# openmv.net
KiCad netlist of a schematic drawn in EAGLE
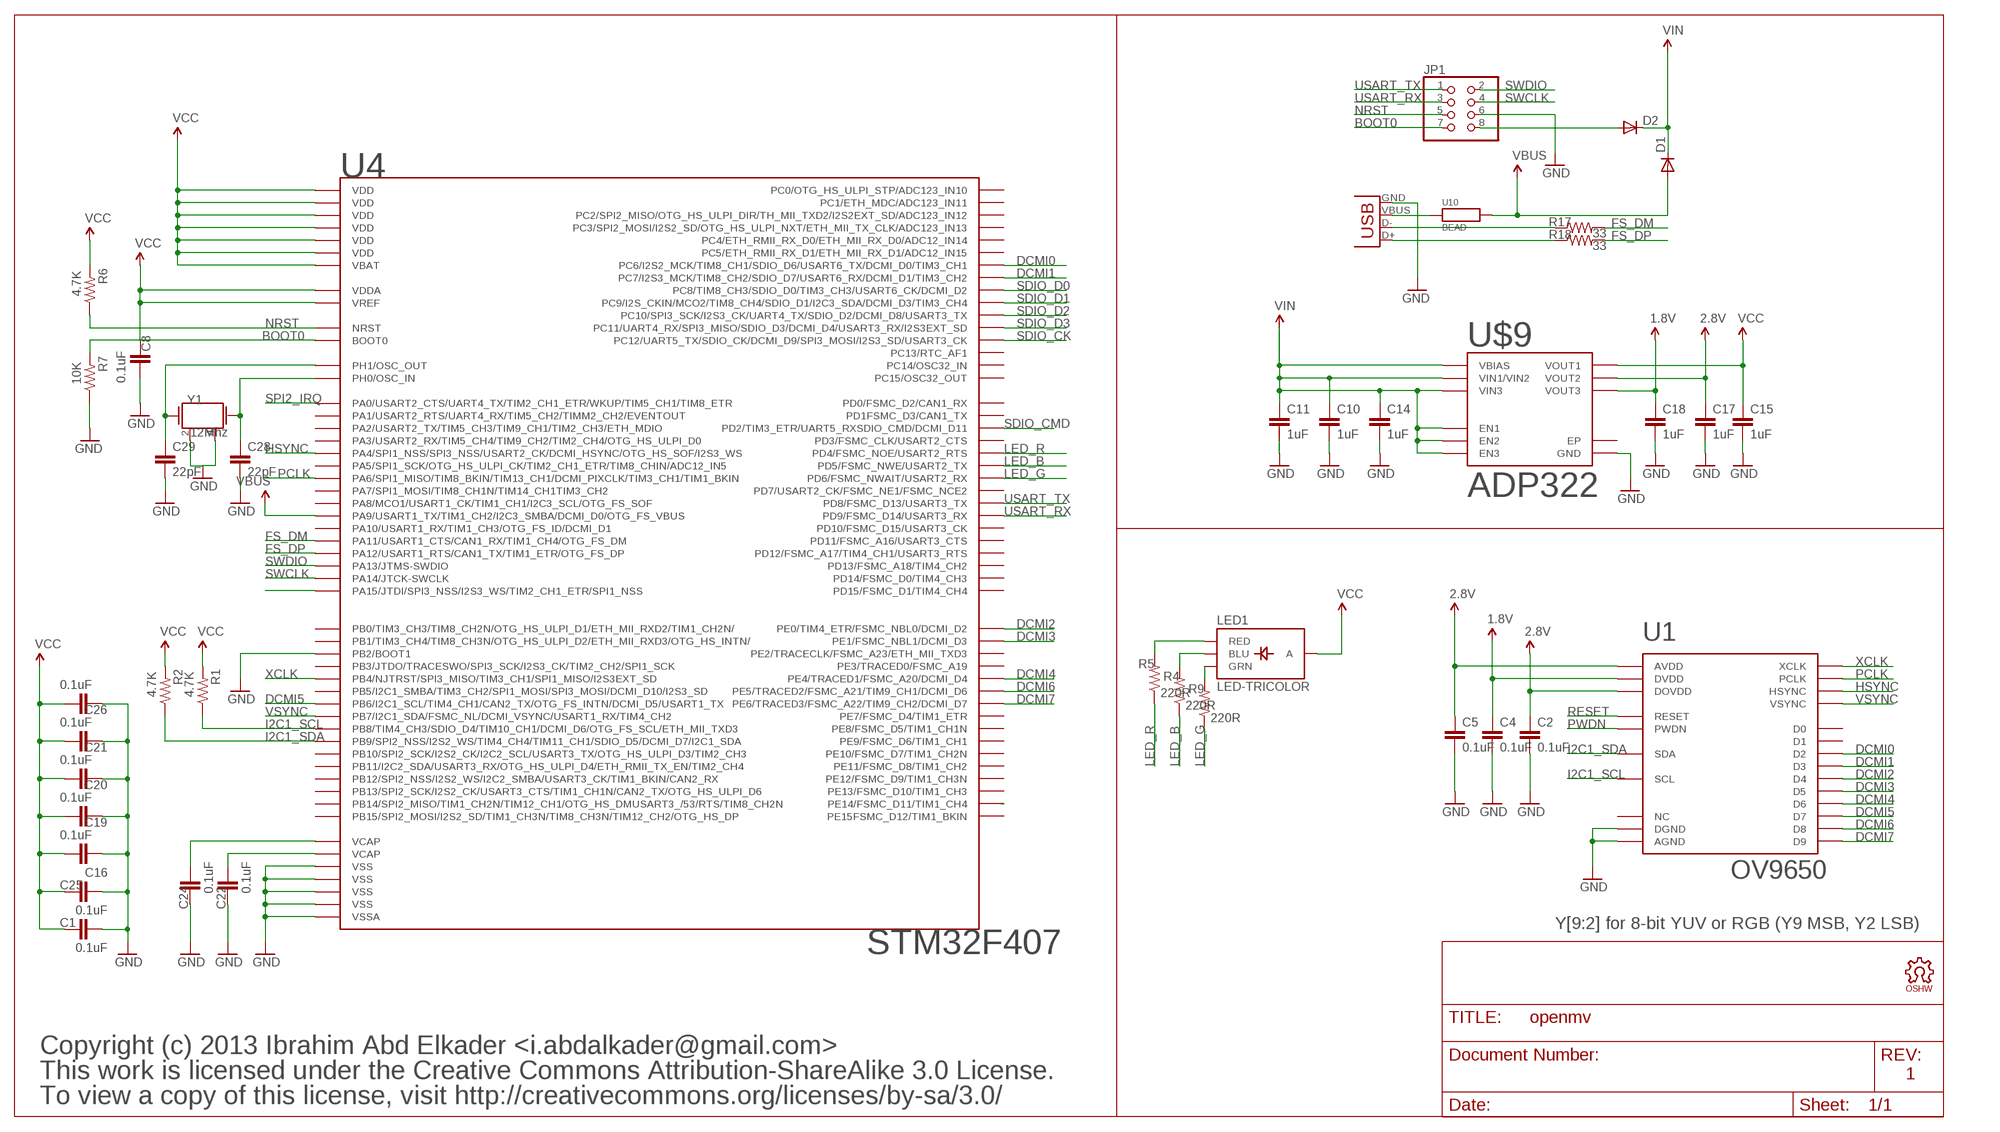
[diagram p0: schematic, sheet 1]

(export (version "E")
  (design (tool "Eeschema 10.0.6"))
  (components
    (comp (ref "C1")
      (value "0.1uF")
      (footprint "eagle-import:0402-CAP")
      (libsource (lib "eagle-import") (part "CAP0402-CAP"))
    )
    (comp (ref "C2")
      (value "0.1uF")
      (footprint "eagle-import:0402-CAP")
      (libsource (lib "eagle-import") (part "CAP0402-CAP"))
    )
    (comp (ref "C4")
      (value "0.1uF")
      (footprint "eagle-import:0402-CAP")
      (libsource (lib "eagle-import") (part "CAP0402-CAP"))
    )
    (comp (ref "C5")
      (value "0.1uF")
      (footprint "eagle-import:0402-CAP")
      (libsource (lib "eagle-import") (part "CAP0402-CAP"))
    )
    (comp (ref "C8")
      (value "0.1uF")
      (footprint "eagle-import:0402-CAP")
      (libsource (lib "eagle-import") (part "CAP0402-CAP"))
    )
    (comp (ref "C10")
      (value "1uF")
      (footprint "eagle-import:0402-CAP")
      (libsource (lib "eagle-import") (part "CAP0402-CAP"))
    )
    (comp (ref "C11")
      (value "1uF")
      (footprint "eagle-import:0402-CAP")
      (libsource (lib "eagle-import") (part "CAP0402-CAP"))
    )
    (comp (ref "C14")
      (value "1uF")
      (footprint "eagle-import:0402-CAP")
      (libsource (lib "eagle-import") (part "CAP0402-CAP"))
    )
    (comp (ref "C15")
      (value "1uF")
      (footprint "eagle-import:0402-CAP")
      (libsource (lib "eagle-import") (part "CAP0402-CAP"))
    )
    (comp (ref "C16")
      (value "0.1uF")
      (footprint "eagle-import:0402-CAP")
      (libsource (lib "eagle-import") (part "CAP0402-CAP"))
    )
    (comp (ref "C17")
      (value "1uF")
      (footprint "eagle-import:0402-CAP")
      (libsource (lib "eagle-import") (part "CAP0402-CAP"))
    )
    (comp (ref "C18")
      (value "1uF")
      (footprint "eagle-import:0402-CAP")
      (libsource (lib "eagle-import") (part "CAP0402-CAP"))
    )
    (comp (ref "C19")
      (value "0.1uF")
      (footprint "eagle-import:0402-CAP")
      (libsource (lib "eagle-import") (part "CAP0402-CAP"))
    )
    (comp (ref "C20")
      (value "0.1uF")
      (footprint "eagle-import:0402-CAP")
      (libsource (lib "eagle-import") (part "CAP0402-CAP"))
    )
    (comp (ref "C21")
      (value "0.1uF")
      (footprint "eagle-import:0402-CAP")
      (libsource (lib "eagle-import") (part "CAP0402-CAP"))
    )
    (comp (ref "C22")
      (value "0.1uF")
      (footprint "eagle-import:0402-CAP")
      (libsource (lib "eagle-import") (part "CAP0402-CAP"))
    )
    (comp (ref "C24")
      (value "0.1uF")
      (footprint "eagle-import:0402-CAP")
      (libsource (lib "eagle-import") (part "CAP0402-CAP"))
    )
    (comp (ref "C25")
      (value "0.1uF")
      (footprint "eagle-import:0402-CAP")
      (libsource (lib "eagle-import") (part "CAP0402-CAP"))
    )
    (comp (ref "C26")
      (value "0.1uF")
      (footprint "eagle-import:0402-CAP")
      (libsource (lib "eagle-import") (part "CAP0402-CAP"))
    )
    (comp (ref "C28")
      (value "22pF")
      (footprint "eagle-import:0402-CAP")
      (libsource (lib "eagle-import") (part "CAP0402-CAP"))
    )
    (comp (ref "C29")
      (value "22pF")
      (footprint "eagle-import:0402-CAP")
      (libsource (lib "eagle-import") (part "CAP0402-CAP"))
    )
    (comp (ref "D1")
      (value "DIODESOD")
      (footprint "eagle-import:SOD-323")
      (libsource (lib "eagle-import") (part "DIODESOD"))
    )
    (comp (ref "D2")
      (value "DIODESOD")
      (footprint "eagle-import:SOD-323")
      (libsource (lib "eagle-import") (part "DIODESOD"))
    )
    (comp (ref "JP1")
      (value "PINHD-2X4")
      (footprint "eagle-import:2X04")
      (libsource (lib "eagle-import") (part "PINHD-2X4"))
    )
    (comp (ref "LED1")
      (value "LED-TRICOLOR")
      (footprint "eagle-import:LED-TRICOLOR-SMD")
      (libsource (lib "eagle-import") (part "LED-TRICOLOR"))
    )
    (comp (ref "LOGO2")
      (value "OSHW_LOGO_FILLX0100-NT")
      (footprint "eagle-import:OSHW_FILLX100_NOTEXT")
      (libsource (lib "eagle-import") (part "OSHW_LOGO_FILLX0100-NT"))
    )
    (comp (ref "R1")
      (value "4.7K")
      (footprint "eagle-import:0402-RES")
      (libsource (lib "eagle-import") (part "RESISTOR0402-RES"))
    )
    (comp (ref "R2")
      (value "4.7K")
      (footprint "eagle-import:0402-RES")
      (libsource (lib "eagle-import") (part "RESISTOR0402-RES"))
    )
    (comp (ref "R4")
      (value "220R")
      (footprint "eagle-import:0402-RES")
      (libsource (lib "eagle-import") (part "RESISTOR0402-RES"))
    )
    (comp (ref "R5")
      (value "220R")
      (footprint "eagle-import:0402-RES")
      (libsource (lib "eagle-import") (part "RESISTOR0402-RES"))
    )
    (comp (ref "R6")
      (value "4.7K")
      (footprint "eagle-import:0402-RES")
      (libsource (lib "eagle-import") (part "RESISTOR0402-RES"))
    )
    (comp (ref "R7")
      (value "10K")
      (footprint "eagle-import:0402-RES")
      (libsource (lib "eagle-import") (part "RESISTOR0402-RES"))
    )
    (comp (ref "R9")
      (value "220R")
      (footprint "eagle-import:0402-RES")
      (libsource (lib "eagle-import") (part "RESISTOR0402-RES"))
    )
    (comp (ref "R17")
      (value "33")
      (footprint "eagle-import:0402-RES")
      (libsource (lib "eagle-import") (part "RESISTOR0402-RES"))
    )
    (comp (ref "R18")
      (value "33")
      (footprint "eagle-import:0402-RES")
      (libsource (lib "eagle-import") (part "RESISTOR0402-RES"))
    )
    (comp (ref "U$9")
      (value "ADP322")
      (footprint "eagle-import:WFQFN-16")
      (libsource (lib "eagle-import") (part "ADP322"))
    )
    (comp (ref "U1")
      (value "OV9650")
      (footprint "eagle-import:OV9650")
      (libsource (lib "eagle-import") (part "OV9650"))
    )
    (comp (ref "U4")
      (value "STM32F407")
      (footprint "eagle-import:LQFP100")
      (libsource (lib "eagle-import") (part "STM32F407"))
    )
    (comp (ref "U10")
      (value "BEAD")
      (footprint "eagle-import:0402-CAP")
      (libsource (lib "eagle-import") (part "BEAD"))
    )
    (comp (ref "X2")
      (value "USB-MICROB")
      (footprint "eagle-import:USB-MICROB")
      (libsource (lib "eagle-import") (part "USB-MICROB"))
    )
    (comp (ref "Y1")
      (value "12Mhz")
      (footprint "eagle-import:CRYSTAL-SMD-5X3")
      (libsource (lib "eagle-import") (part "CRYSTAL5X3"))
    )
  )
  (nets
    (net (code "1") (name "/BOOT0") (class "Default")
      (node (ref "JP1") (pin "7") (pinfunction "7_7") (pintype "passive"))
      (node (ref "R7") (pin "2") (pinfunction "2_2") (pintype "passive"))
      (node (ref "U4") (pin "94") (pinfunction "BOOT0_94") (pintype "bidirectional"))
    )
    (net (code "2") (name "/DCMI0") (class "Default")
      (node (ref "U1") (pin "P$19") (pinfunction "D2_P$19") (pintype "bidirectional"))
      (node (ref "U4") (pin "63") (pinfunction "PC6/I2S2_MCK/TIM8_CH1/SDIO_D6/USART6_TX/DCMI_D0/TIM3_CH1_63") (pintype "bidirectional"))
    )
    (net (code "3") (name "/DCMI1") (class "Default")
      (node (ref "U1") (pin "P$21") (pinfunction "D3_P$21") (pintype "bidirectional"))
      (node (ref "U4") (pin "64") (pinfunction "PC7/I2S3_MCK/TIM8_CH2/SDIO_D7/USART6_RX/DCMI_D1/TIM3_CH2_64") (pintype "bidirectional"))
    )
    (net (code "4") (name "/DCMI2") (class "Default")
      (node (ref "U1") (pin "P$22") (pinfunction "D4_P$22") (pintype "bidirectional"))
      (node (ref "U4") (pin "97") (pinfunction "PE0/TIM4_ETR/FSMC_NBL0/DCMI_D2_97") (pintype "bidirectional"))
    )
    (net (code "5") (name "/DCMI3") (class "Default")
      (node (ref "U1") (pin "P$20") (pinfunction "D5_P$20") (pintype "bidirectional"))
      (node (ref "U4") (pin "98") (pinfunction "PE1/FSMC_NBL1/DCMI_D3_98") (pintype "bidirectional"))
    )
    (net (code "6") (name "/DCMI4") (class "Default")
      (node (ref "U1") (pin "P$18") (pinfunction "D6_P$18") (pintype "bidirectional"))
      (node (ref "U4") (pin "3") (pinfunction "PE4/TRACED1/FSMC_A20/DCMI_D4_3") (pintype "bidirectional"))
    )
    (net (code "7") (name "/DCMI5") (class "Default")
      (node (ref "U1") (pin "P$16") (pinfunction "D7_P$16") (pintype "bidirectional"))
      (node (ref "U4") (pin "92") (pinfunction "PB6/I2C1_SCL/TIM4_CH1/CAN2_TX/OTG_FS_INTN/DCMI_D5/USART1_TX_92") (pintype "bidirectional"))
    )
    (net (code "8") (name "/DCMI6") (class "Default")
      (node (ref "U1") (pin "P$14") (pinfunction "D8_P$14") (pintype "bidirectional"))
      (node (ref "U4") (pin "4") (pinfunction "PE5/TRACED2/FSMC_A21/TIM9_CH1/DCMI_D6_4") (pintype "bidirectional"))
    )
    (net (code "9") (name "/DCMI7") (class "Default")
      (node (ref "U1") (pin "P$12") (pinfunction "D9_P$12") (pintype "bidirectional"))
      (node (ref "U4") (pin "5") (pinfunction "PE6/TRACED3/FSMC_A22/TIM9_CH2/DCMI_D7_5") (pintype "bidirectional"))
    )
    (net (code "10") (name "/FS_DM") (class "Default")
      (node (ref "R17") (pin "2") (pinfunction "2_2") (pintype "passive"))
      (node (ref "U4") (pin "70") (pinfunction "PA11/USART1_CTS/CAN1_RX/TIM1_CH4/OTG_FS_DM_70") (pintype "bidirectional"))
    )
    (net (code "11") (name "/FS_DP") (class "Default")
      (node (ref "R18") (pin "2") (pinfunction "2_2") (pintype "passive"))
      (node (ref "U4") (pin "71") (pinfunction "PA12/USART1_RTS/CAN1_TX/TIM1_ETR/OTG_FS_DP_71") (pintype "bidirectional"))
    )
    (net (code "12") (name "/HSYNC") (class "Default")
      (node (ref "U1") (pin "P$9") (pinfunction "HSYNC_P$9") (pintype "bidirectional"))
      (node (ref "U4") (pin "29") (pinfunction "PA4/SPI1_NSS/SPI3_NSS/USART2_CK/DCMI_HSYNC/OTG_HS_SOF/I2S3_WS_29") (pintype "bidirectional"))
    )
    (net (code "13") (name "/I2C1_SCL") (class "Default")
      (node (ref "R1") (pin "1") (pinfunction "1_1") (pintype "passive"))
      (node (ref "U1") (pin "P$5") (pinfunction "SCL_P$5") (pintype "bidirectional"))
      (node (ref "U4") (pin "95") (pinfunction "PB8/TIM4_CH3/SDIO_D4/TIM10_CH1/DCMI_D6/OTG_FS_SCL/ETH_MII_TXD3_95") (pintype "bidirectional"))
    )
    (net (code "14") (name "/I2C1_SDA") (class "Default")
      (node (ref "R2") (pin "1") (pinfunction "1_1") (pintype "passive"))
      (node (ref "U1") (pin "P$3") (pinfunction "SDA_P$3") (pintype "bidirectional"))
      (node (ref "U4") (pin "96") (pinfunction "PB9/SPI2_NSS/I2S2_WS/TIM4_CH4/TIM11_CH1/SDIO_D5/DCMI_D7/I2C1_SDA_96") (pintype "bidirectional"))
    )
    (net (code "15") (name "/LED_B") (class "Default")
      (node (ref "R4") (pin "1") (pinfunction "1_1") (pintype "passive"))
      (node (ref "U4") (pin "86") (pinfunction "PD5/FSMC_NWE/USART2_TX_86") (pintype "bidirectional"))
    )
    (net (code "16") (name "/LED_G") (class "Default")
      (node (ref "R9") (pin "1") (pinfunction "1_1") (pintype "passive"))
      (node (ref "U4") (pin "87") (pinfunction "PD6/FSMC_NWAIT/USART2_RX_87") (pintype "bidirectional"))
    )
    (net (code "17") (name "/LED_R") (class "Default")
      (node (ref "R5") (pin "1") (pinfunction "1_1") (pintype "passive"))
      (node (ref "U4") (pin "85") (pinfunction "PD4/FSMC_NOE/USART2_RTS_85") (pintype "bidirectional"))
    )
    (net (code "18") (name "/NRST") (class "Default")
      (node (ref "JP1") (pin "5") (pinfunction "5_5") (pintype "passive"))
      (node (ref "R6") (pin "1") (pinfunction "1_1") (pintype "passive"))
      (node (ref "U4") (pin "14") (pinfunction "NRST_14") (pintype "bidirectional"))
    )
    (net (code "19") (name "/PCLK") (class "Default")
      (node (ref "U1") (pin "P$17") (pinfunction "PCLK_P$17") (pintype "bidirectional"))
      (node (ref "U4") (pin "31") (pinfunction "PA6/SPI1_MISO/TIM8_BKIN/TIM13_CH1/DCMI_PIXCLK/TIM3_CH1/TIM1_BKIN_31") (pintype "bidirectional"))
    )
    (net (code "20") (name "/PWDN") (class "Default")
      (node (ref "U1") (pin "P$8") (pinfunction "PWDN_P$8") (pintype "bidirectional"))
    )
    (net (code "21") (name "/RESET") (class "Default")
      (node (ref "U1") (pin "P$6") (pinfunction "RESET_P$6") (pintype "bidirectional"))
    )
    (net (code "22") (name "/SDIO_CK") (class "Default")
      (node (ref "U4") (pin "80") (pinfunction "PC12/UART5_TX/SDIO_CK/DCMI_D9/SPI3_MOSI/I2S3_SD/USART3_CK_80") (pintype "bidirectional"))
    )
    (net (code "23") (name "/SDIO_CMD") (class "Default")
      (node (ref "U4") (pin "83") (pinfunction "PD2/TIM3_ETR/UART5_RXSDIO_CMD/DCMI_D11_83") (pintype "bidirectional"))
    )
    (net (code "24") (name "/SDIO_D0") (class "Default")
      (node (ref "U4") (pin "65") (pinfunction "PC8/TIM8_CH3/SDIO_D0/TIM3_CH3/USART6_CK/DCMI_D2_65") (pintype "bidirectional"))
    )
    (net (code "25") (name "/SDIO_D1") (class "Default")
      (node (ref "U4") (pin "66") (pinfunction "PC9/I2S_CKIN/MCO2/TIM8_CH4/SDIO_D1/I2C3_SDA/DCMI_D3/TIM3_CH4_66") (pintype "bidirectional"))
    )
    (net (code "26") (name "/SDIO_D2") (class "Default")
      (node (ref "U4") (pin "78") (pinfunction "PC10/SPI3_SCK/I2S3_CK/UART4_TX/SDIO_D2/DCMI_D8/USART3_TX_78") (pintype "bidirectional"))
    )
    (net (code "27") (name "/SDIO_D3") (class "Default")
      (node (ref "U4") (pin "79") (pinfunction "PC11/UART4_RX/SPI3_MISO/SDIO_D3/DCMI_D4/USART3_RX/I2S3EXT_SD_79") (pintype "bidirectional"))
    )
    (net (code "28") (name "/SPI2_IRQ") (class "Default")
      (node (ref "U4") (pin "23") (pinfunction "PA0/USART2_CTS/UART4_TX/TIM2_CH1_ETR/WKUP/TIM5_CH1/TIM8_ETR_23") (pintype "bidirectional"))
    )
    (net (code "29") (name "/SWCLK") (class "Default")
      (node (ref "JP1") (pin "4") (pinfunction "4_4") (pintype "passive"))
      (node (ref "U4") (pin "76") (pinfunction "PA14/JTCK-SWCLK_76") (pintype "bidirectional"))
    )
    (net (code "30") (name "/SWDIO") (class "Default")
      (node (ref "JP1") (pin "2") (pinfunction "2_2") (pintype "passive"))
      (node (ref "U4") (pin "72") (pinfunction "PA13/JTMS-SWDIO_72") (pintype "bidirectional"))
    )
    (net (code "31") (name "/USART_RX") (class "Default")
      (node (ref "JP1") (pin "3") (pinfunction "3_3") (pintype "passive"))
      (node (ref "U4") (pin "56") (pinfunction "PD9/FSMC_D14/USART3_RX_56") (pintype "bidirectional"))
    )
    (net (code "32") (name "/USART_TX") (class "Default")
      (node (ref "JP1") (pin "1") (pinfunction "1_1") (pintype "passive"))
      (node (ref "U4") (pin "55") (pinfunction "PD8/FSMC_D13/USART3_TX_55") (pintype "bidirectional"))
    )
    (net (code "33") (name "/VSYNC") (class "Default")
      (node (ref "U1") (pin "P$7") (pinfunction "VSYNC_P$7") (pintype "bidirectional"))
      (node (ref "U4") (pin "93") (pinfunction "PB7/I2C1_SDA/FSMC_NL/DCMI_VSYNC/USART1_RX/TIM4_CH2_93") (pintype "bidirectional"))
    )
    (net (code "34") (name "/XCLK") (class "Default")
      (node (ref "U1") (pin "P$13") (pinfunction "XCLK_P$13") (pintype "bidirectional"))
      (node (ref "U4") (pin "90") (pinfunction "PB4/NJTRST/SPI3_MISO/TIM3_CH1/SPI1_MISO/I2S3EXT_SD_90") (pintype "bidirectional"))
    )
    (net (code "35") (name "1.8V") (class "Default")
      (node (ref "C18") (pin "1") (pinfunction "1_1") (pintype "passive"))
      (node (ref "C4") (pin "1") (pinfunction "1_1") (pintype "passive"))
      (node (ref "U$9") (pin "8") (pinfunction "VOUT3_8") (pintype "passive"))
      (node (ref "U1") (pin "P$10") (pinfunction "DVDD_P$10") (pintype "bidirectional"))
    )
    (net (code "36") (name "2.8V") (class "Default")
      (node (ref "C17") (pin "1") (pinfunction "1_1") (pintype "passive"))
      (node (ref "C2") (pin "1") (pinfunction "1_1") (pintype "passive"))
      (node (ref "C5") (pin "1") (pinfunction "1_1") (pintype "passive"))
      (node (ref "U$9") (pin "6") (pinfunction "VOUT2_6") (pintype "passive"))
      (node (ref "U1") (pin "P$11") (pinfunction "DOVDD_P$11") (pintype "bidirectional"))
      (node (ref "U1") (pin "P$4") (pinfunction "AVDD_P$4") (pintype "power_in"))
    )
    (net (code "37") (name "GND") (class "Default")
      (node (ref "C1") (pin "1") (pinfunction "1_1") (pintype "passive"))
      (node (ref "C10") (pin "2") (pinfunction "2_2") (pintype "passive"))
      (node (ref "C11") (pin "2") (pinfunction "2_2") (pintype "passive"))
      (node (ref "C14") (pin "2") (pinfunction "2_2") (pintype "passive"))
      (node (ref "C15") (pin "2") (pinfunction "2_2") (pintype "passive"))
      (node (ref "C16") (pin "1") (pinfunction "1_1") (pintype "passive"))
      (node (ref "C17") (pin "2") (pinfunction "2_2") (pintype "passive"))
      (node (ref "C18") (pin "2") (pinfunction "2_2") (pintype "passive"))
      (node (ref "C19") (pin "2") (pinfunction "2_2") (pintype "passive"))
      (node (ref "C2") (pin "2") (pinfunction "2_2") (pintype "passive"))
      (node (ref "C20") (pin "2") (pinfunction "2_2") (pintype "passive"))
      (node (ref "C21") (pin "2") (pinfunction "2_2") (pintype "passive"))
      (node (ref "C22") (pin "2") (pinfunction "2_2") (pintype "passive"))
      (node (ref "C24") (pin "2") (pinfunction "2_2") (pintype "passive"))
      (node (ref "C25") (pin "1") (pinfunction "1_1") (pintype "passive"))
      (node (ref "C26") (pin "2") (pinfunction "2_2") (pintype "passive"))
      (node (ref "C28") (pin "2") (pinfunction "2_2") (pintype "passive"))
      (node (ref "C29") (pin "2") (pinfunction "2_2") (pintype "passive"))
      (node (ref "C4") (pin "2") (pinfunction "2_2") (pintype "passive"))
      (node (ref "C5") (pin "2") (pinfunction "2_2") (pintype "passive"))
      (node (ref "C8") (pin "1") (pinfunction "1_1") (pintype "passive"))
      (node (ref "JP1") (pin "6") (pinfunction "6_6") (pintype "passive"))
      (node (ref "R7") (pin "1") (pinfunction "1_1") (pintype "passive"))
      (node (ref "U$9") (pin "12") (pinfunction "GND_12") (pintype "power_in"))
      (node (ref "U1") (pin "P$15") (pinfunction "DGND_P$15") (pintype "bidirectional"))
      (node (ref "U1") (pin "P$2") (pinfunction "AGND_P$2") (pintype "power_in"))
      (node (ref "U4") (pin "10") (pinfunction "VSS_10") (pintype "power_in"))
      (node (ref "U4") (pin "20") (pinfunction "VSSA_20") (pintype "power_in"))
      (node (ref "U4") (pin "27") (pinfunction "VSS_27") (pintype "power_in"))
      (node (ref "U4") (pin "37") (pinfunction "PB2/BOOT1_37") (pintype "bidirectional"))
      (node (ref "U4") (pin "74") (pinfunction "VSS_74") (pintype "power_in"))
      (node (ref "U4") (pin "99") (pinfunction "VSS_99") (pintype "power_in"))
      (node (ref "X2") (pin "GND") (pinfunction "GND_GND") (pintype "bidirectional"))
      (node (ref "Y1") (pin "2") (pinfunction "P$1_2") (pintype "power_in"))
      (node (ref "Y1") (pin "4") (pinfunction "P$2_4") (pintype "power_in"))
    )
    (net (code "38") (name "Net-(C22-Pad1)") (class "Default")
      (node (ref "C22") (pin "1") (pinfunction "1_1") (pintype "passive"))
      (node (ref "U4") (pin "73") (pinfunction "VCAP_73") (pintype "power_in"))
    )
    (net (code "39") (name "Net-(C24-Pad1)") (class "Default")
      (node (ref "C24") (pin "1") (pinfunction "1_1") (pintype "passive"))
      (node (ref "U4") (pin "49") (pinfunction "VCAP_49") (pintype "power_in"))
    )
    (net (code "40") (name "Net-(D2-A)") (class "Default")
      (node (ref "D2") (pin "2") (pinfunction "A_2") (pintype "passive"))
      (node (ref "JP1") (pin "8") (pinfunction "8_8") (pintype "passive"))
    )
    (net (code "41") (name "Net-(LED1-BLU)") (class "Default")
      (node (ref "LED1") (pin "B") (pinfunction "BLU_B") (pintype "bidirectional"))
      (node (ref "R4") (pin "2") (pinfunction "2_2") (pintype "passive"))
    )
    (net (code "42") (name "Net-(LED1-GRN)") (class "Default")
      (node (ref "LED1") (pin "G") (pinfunction "GRN_G") (pintype "bidirectional"))
      (node (ref "R9") (pin "2") (pinfunction "2_2") (pintype "passive"))
    )
    (net (code "43") (name "Net-(LED1-RED)") (class "Default")
      (node (ref "LED1") (pin "R") (pinfunction "RED_R") (pintype "bidirectional"))
      (node (ref "R5") (pin "2") (pinfunction "2_2") (pintype "passive"))
    )
    (net (code "44") (name "Net-(R17-Pad1)") (class "Default")
      (node (ref "R17") (pin "1") (pinfunction "1_1") (pintype "passive"))
      (node (ref "X2") (pin "D-") (pinfunction "D-_D-") (pintype "bidirectional"))
    )
    (net (code "45") (name "Net-(R18-Pad1)") (class "Default")
      (node (ref "R18") (pin "1") (pinfunction "1_1") (pintype "passive"))
      (node (ref "X2") (pin "D+") (pinfunction "D+_D+") (pintype "bidirectional"))
    )
    (net (code "46") (name "Net-(U4-PH0{slash}OSC_IN)") (class "Default")
      (node (ref "C28") (pin "1") (pinfunction "1_1") (pintype "passive"))
      (node (ref "U4") (pin "12") (pinfunction "PH0/OSC_IN_12") (pintype "bidirectional"))
      (node (ref "Y1") (pin "3") (pinfunction "2_3") (pintype "passive"))
    )
    (net (code "47") (name "Net-(U4-PH1{slash}OSC_OUT)") (class "Default")
      (node (ref "C29") (pin "1") (pinfunction "1_1") (pintype "passive"))
      (node (ref "U4") (pin "13") (pinfunction "PH1/OSC_OUT_13") (pintype "bidirectional"))
      (node (ref "Y1") (pin "1") (pinfunction "1_1") (pintype "passive"))
    )
    (net (code "48") (name "Net-(U10-Pad1)") (class "Default")
      (node (ref "U10") (pin "1") (pinfunction "1_1") (pintype "passive"))
      (node (ref "X2") (pin "VBUS") (pinfunction "VBUS_VBUS") (pintype "bidirectional"))
    )
    (net (code "49") (name "VBUS") (class "Default")
      (node (ref "D1") (pin "2") (pinfunction "A_2") (pintype "passive"))
      (node (ref "U10") (pin "2") (pinfunction "2_2") (pintype "passive"))
      (node (ref "U4") (pin "68") (pinfunction "PA9/USART1_TX/TIM1_CH2/I2C3_SMBA/DCMI_D0/OTG_FS_VBUS_68") (pintype "bidirectional"))
    )
    (net (code "50") (name "VCC") (class "Default")
      (node (ref "C1") (pin "2") (pinfunction "2_2") (pintype "passive"))
      (node (ref "C15") (pin "1") (pinfunction "1_1") (pintype "passive"))
      (node (ref "C16") (pin "2") (pinfunction "2_2") (pintype "passive"))
      (node (ref "C19") (pin "1") (pinfunction "1_1") (pintype "passive"))
      (node (ref "C20") (pin "1") (pinfunction "1_1") (pintype "passive"))
      (node (ref "C21") (pin "1") (pinfunction "1_1") (pintype "passive"))
      (node (ref "C25") (pin "2") (pinfunction "2_2") (pintype "passive"))
      (node (ref "C26") (pin "1") (pinfunction "1_1") (pintype "passive"))
      (node (ref "C8") (pin "2") (pinfunction "2_2") (pintype "passive"))
      (node (ref "LED1") (pin "A") (pinfunction "A_A") (pintype "bidirectional"))
      (node (ref "R1") (pin "2") (pinfunction "2_2") (pintype "passive"))
      (node (ref "R2") (pin "2") (pinfunction "2_2") (pintype "passive"))
      (node (ref "R6") (pin "2") (pinfunction "2_2") (pintype "passive"))
      (node (ref "U$9") (pin "5") (pinfunction "VOUT1_5") (pintype "passive"))
      (node (ref "U4") (pin "100") (pinfunction "VDD_100") (pintype "power_in"))
      (node (ref "U4") (pin "11") (pinfunction "VDD_11") (pintype "power_in"))
      (node (ref "U4") (pin "19") (pinfunction "VDD_19") (pintype "power_in"))
      (node (ref "U4") (pin "21") (pinfunction "VREF_21") (pintype "power_in"))
      (node (ref "U4") (pin "22") (pinfunction "VDDA_22") (pintype "power_in"))
      (node (ref "U4") (pin "28") (pinfunction "VDD_28") (pintype "power_in"))
      (node (ref "U4") (pin "50") (pinfunction "VDD_50") (pintype "power_in"))
      (node (ref "U4") (pin "6") (pinfunction "VBAT_6") (pintype "power_in"))
      (node (ref "U4") (pin "75") (pinfunction "VDD_75") (pintype "power_in"))
    )
    (net (code "51") (name "VIN") (class "Default")
      (node (ref "C10") (pin "1") (pinfunction "1_1") (pintype "passive"))
      (node (ref "C11") (pin "1") (pinfunction "1_1") (pintype "passive"))
      (node (ref "C14") (pin "1") (pinfunction "1_1") (pintype "passive"))
      (node (ref "D1") (pin "1") (pinfunction "C_1") (pintype "passive"))
      (node (ref "D2") (pin "1") (pinfunction "C_1") (pintype "passive"))
      (node (ref "U$9") (pin "1") (pinfunction "EN1_1") (pintype "passive"))
      (node (ref "U$9") (pin "10") (pinfunction "VIN3_10") (pintype "power_in"))
      (node (ref "U$9") (pin "15") (pinfunction "EN3_15") (pintype "passive"))
      (node (ref "U$9") (pin "16") (pinfunction "EN2_16") (pintype "passive"))
      (node (ref "U$9") (pin "2") (pinfunction "VBIAS_2") (pintype "power_in"))
      (node (ref "U$9") (pin "3") (pinfunction "VIN1/VIN2_3") (pintype "power_in"))
    )
    (net (code "52") (name "unconnected-(U$9A-EP-PadEXP)") (class "Default")
      (node (ref "U$9") (pin "EXP") (pinfunction "EP_EXP") (pintype "input"))
    )
    (net (code "53") (name "unconnected-(U1-D0-PadP$24)") (class "Default")
      (node (ref "U1") (pin "P$24") (pinfunction "D0_P$24") (pintype "bidirectional"))
    )
    (net (code "54") (name "unconnected-(U1-D1-PadP$23)") (class "Default")
      (node (ref "U1") (pin "P$23") (pinfunction "D1_P$23") (pintype "bidirectional"))
    )
    (net (code "55") (name "unconnected-(U1-NC-PadP$1)") (class "Default")
      (node (ref "U1") (pin "P$1") (pinfunction "NC_P$1") (pintype "no_connect"))
    )
    (net (code "56") (name "unconnected-(U4-PA1{slash}USART2_RTS{slash}UART4_RX{slash}TIM5_CH2{slash}TIMM2_CH2{slash}EVENTOUT-Pad24)") (class "Default")
      (node (ref "U4") (pin "24") (pinfunction "PA1/USART2_RTS/UART4_RX/TIM5_CH2/TIMM2_CH2/EVENTOUT_24") (pintype "bidirectional"))
    )
    (net (code "57") (name "unconnected-(U4-PA2{slash}USART2_TX{slash}TIM5_CH3{slash}TIM9_CH1{slash}TIM2_CH3{slash}ETH_MDIO-Pad25)") (class "Default")
      (node (ref "U4") (pin "25") (pinfunction "PA2/USART2_TX/TIM5_CH3/TIM9_CH1/TIM2_CH3/ETH_MDIO_25") (pintype "bidirectional"))
    )
    (net (code "58") (name "unconnected-(U4-PA3{slash}USART2_RX{slash}TIM5_CH4{slash}TIM9_CH2{slash}TIM2_CH4{slash}OTG_HS_ULPI_D0-Pad26)") (class "Default")
      (node (ref "U4") (pin "26") (pinfunction "PA3/USART2_RX/TIM5_CH4/TIM9_CH2/TIM2_CH4/OTG_HS_ULPI_D0_26") (pintype "bidirectional"))
    )
    (net (code "59") (name "unconnected-(U4-PA5{slash}SPI1_SCK{slash}OTG_HS_ULPI_CK{slash}TIM2_CH1_ETR{slash}TIM8_CHIN{slash}ADC12_IN5-Pad30)") (class "Default")
      (node (ref "U4") (pin "30") (pinfunction "PA5/SPI1_SCK/OTG_HS_ULPI_CK/TIM2_CH1_ETR/TIM8_CHIN/ADC12_IN5_30") (pintype "bidirectional"))
    )
    (net (code "60") (name "unconnected-(U4-PA7{slash}SPI1_MOSI{slash}TIM8_CH1N{slash}TIM14_CH1TIM3_CH2-Pad32)") (class "Default")
      (node (ref "U4") (pin "32") (pinfunction "PA7/SPI1_MOSI/TIM8_CH1N/TIM14_CH1TIM3_CH2_32") (pintype "bidirectional"))
    )
    (net (code "61") (name "unconnected-(U4-PA8{slash}MCO1{slash}USART1_CK{slash}TIM1_CH1{slash}I2C3_SCL{slash}OTG_FS_SOF-Pad67)") (class "Default")
      (node (ref "U4") (pin "67") (pinfunction "PA8/MCO1/USART1_CK/TIM1_CH1/I2C3_SCL/OTG_FS_SOF_67") (pintype "bidirectional"))
    )
    (net (code "62") (name "unconnected-(U4-PA10{slash}USART1_RX{slash}TIM1_CH3{slash}OTG_FS_ID{slash}DCMI_D1-Pad69)") (class "Default")
      (node (ref "U4") (pin "69") (pinfunction "PA10/USART1_RX/TIM1_CH3/OTG_FS_ID/DCMI_D1_69") (pintype "bidirectional"))
    )
    (net (code "63") (name "unconnected-(U4-PA15{slash}JTDI{slash}SPI3_NSS{slash}I2S3_WS{slash}TIM2_CH1_ETR{slash}SPI1_NSS-Pad77)") (class "Default")
      (node (ref "U4") (pin "77") (pinfunction "PA15/JTDI/SPI3_NSS/I2S3_WS/TIM2_CH1_ETR/SPI1_NSS_77") (pintype "bidirectional"))
    )
    (net (code "64") (name "unconnected-(U4-PB0{slash}TIM3_CH3{slash}TIM8_CH2N{slash}OTG_HS_ULPI_D1{slash}ETH_MII_RXD2{slash}TIM1_CH2N{slash}-Pad35)") (class "Default")
      (node (ref "U4") (pin "35") (pinfunction "PB0/TIM3_CH3/TIM8_CH2N/OTG_HS_ULPI_D1/ETH_MII_RXD2/TIM1_CH2N/_35") (pintype "bidirectional"))
    )
    (net (code "65") (name "unconnected-(U4-PB1{slash}TIM3_CH4{slash}TIM8_CH3N{slash}OTG_HS_ULPI_D2{slash}ETH_MII_RXD3{slash}OTG_HS_INTN{slash}-Pad36)") (class "Default")
      (node (ref "U4") (pin "36") (pinfunction "PB1/TIM3_CH4/TIM8_CH3N/OTG_HS_ULPI_D2/ETH_MII_RXD3/OTG_HS_INTN/_36") (pintype "bidirectional"))
    )
    (net (code "66") (name "unconnected-(U4-PB3{slash}JTDO{slash}TRACESWO{slash}SPI3_SCK{slash}I2S3_CK{slash}TIM2_CH2{slash}SPI1_SCK-Pad89)") (class "Default")
      (node (ref "U4") (pin "89") (pinfunction "PB3/JTDO/TRACESWO/SPI3_SCK/I2S3_CK/TIM2_CH2/SPI1_SCK_89") (pintype "bidirectional"))
    )
    (net (code "67") (name "unconnected-(U4-PB5{slash}I2C1_SMBA{slash}TIM3_CH2{slash}SPI1_MOSI{slash}SPI3_MOSI{slash}DCMI_D10{slash}I2S3_SD-Pad91)") (class "Default")
      (node (ref "U4") (pin "91") (pinfunction "PB5/I2C1_SMBA/TIM3_CH2/SPI1_MOSI/SPI3_MOSI/DCMI_D10/I2S3_SD_91") (pintype "bidirectional"))
    )
    (net (code "68") (name "unconnected-(U4-PB10{slash}SPI2_SCK{slash}I2S2_CK{slash}I2C2_SCL{slash}USART3_TX{slash}OTG_HS_ULPI_D3{slash}TIM2_CH3-Pad47)") (class "Default")
      (node (ref "U4") (pin "47") (pinfunction "PB10/SPI2_SCK/I2S2_CK/I2C2_SCL/USART3_TX/OTG_HS_ULPI_D3/TIM2_CH3_47") (pintype "bidirectional"))
    )
    (net (code "69") (name "unconnected-(U4-PB11{slash}I2C2_SDA{slash}USART3_RX{slash}OTG_HS_ULPI_D4{slash}ETH_RMII_TX_EN{slash}TIM2_CH4-Pad48)") (class "Default")
      (node (ref "U4") (pin "48") (pinfunction "PB11/I2C2_SDA/USART3_RX/OTG_HS_ULPI_D4/ETH_RMII_TX_EN/TIM2_CH4_48") (pintype "bidirectional"))
    )
    (net (code "70") (name "unconnected-(U4-PB12{slash}SPI2_NSS{slash}I2S2_WS{slash}I2C2_SMBA{slash}USART3_CK{slash}TIM1_BKIN{slash}CAN2_RX-Pad51)") (class "Default")
      (node (ref "U4") (pin "51") (pinfunction "PB12/SPI2_NSS/I2S2_WS/I2C2_SMBA/USART3_CK/TIM1_BKIN/CAN2_RX_51") (pintype "bidirectional"))
    )
    (net (code "71") (name "unconnected-(U4-PB13{slash}SPI2_SCK{slash}I2S2_CK{slash}USART3_CTS{slash}TIM1_CH1N{slash}CAN2_TX{slash}OTG_HS_ULPI_D6-Pad52)") (class "Default")
      (node (ref "U4") (pin "52") (pinfunction "PB13/SPI2_SCK/I2S2_CK/USART3_CTS/TIM1_CH1N/CAN2_TX/OTG_HS_ULPI_D6_52") (pintype "bidirectional"))
    )
    (net (code "72") (name "unconnected-(U4-PB14{slash}SPI2_MISO{slash}TIM1_CH2N{slash}TIM12_CH1{slash}OTG_HS_DMUSART3_{slash}53{slash}RTS{slash}TIM8_CH2N-Pad53)") (class "Default")
      (node (ref "U4") (pin "53") (pinfunction "PB14/SPI2_MISO/TIM1_CH2N/TIM12_CH1/OTG_HS_DMUSART3_/53/RTS/TIM8_CH2N_53") (pintype "bidirectional"))
    )
    (net (code "73") (name "unconnected-(U4-PB15{slash}SPI2_MOSI{slash}I2S2_SD{slash}TIM1_CH3N{slash}TIM8_CH3N{slash}TIM12_CH2{slash}OTG_HS_DP-Pad54)") (class "Default")
      (node (ref "U4") (pin "54") (pinfunction "PB15/SPI2_MOSI/I2S2_SD/TIM1_CH3N/TIM8_CH3N/TIM12_CH2/OTG_HS_DP_54") (pintype "bidirectional"))
    )
    (net (code "74") (name "unconnected-(U4-PC0{slash}OTG_HS_ULPI_STP{slash}ADC123_IN10-Pad15)") (class "Default")
      (node (ref "U4") (pin "15") (pinfunction "PC0/OTG_HS_ULPI_STP/ADC123_IN10_15") (pintype "bidirectional"))
    )
    (net (code "75") (name "unconnected-(U4-PC1{slash}ETH_MDC{slash}ADC123_IN11-Pad16)") (class "Default")
      (node (ref "U4") (pin "16") (pinfunction "PC1/ETH_MDC/ADC123_IN11_16") (pintype "bidirectional"))
    )
    (net (code "76") (name "unconnected-(U4-PC2{slash}SPI2_MISO{slash}OTG_HS_ULPI_DIR{slash}TH_MII_TXD2{slash}I2S2EXT_SD{slash}ADC123_IN12-Pad17)") (class "Default")
      (node (ref "U4") (pin "17") (pinfunction "PC2/SPI2_MISO/OTG_HS_ULPI_DIR/TH_MII_TXD2/I2S2EXT_SD/ADC123_IN12_17") (pintype "bidirectional"))
    )
    (net (code "77") (name "unconnected-(U4-PC3{slash}SPI2_MOSI{slash}I2S2_SD{slash}OTG_HS_ULPI_NXT{slash}ETH_MII_TX_CLK{slash}ADC123_IN13-Pad18)") (class "Default")
      (node (ref "U4") (pin "18") (pinfunction "PC3/SPI2_MOSI/I2S2_SD/OTG_HS_ULPI_NXT/ETH_MII_TX_CLK/ADC123_IN13_18") (pintype "bidirectional"))
    )
    (net (code "78") (name "unconnected-(U4-PC4{slash}ETH_RMII_RX_D0{slash}ETH_MII_RX_D0{slash}ADC12_IN14-Pad33)") (class "Default")
      (node (ref "U4") (pin "33") (pinfunction "PC4/ETH_RMII_RX_D0/ETH_MII_RX_D0/ADC12_IN14_33") (pintype "bidirectional"))
    )
    (net (code "79") (name "unconnected-(U4-PC5{slash}ETH_RMII_RX_D1{slash}ETH_MII_RX_D1{slash}ADC12_IN15-Pad34)") (class "Default")
      (node (ref "U4") (pin "34") (pinfunction "PC5/ETH_RMII_RX_D1/ETH_MII_RX_D1/ADC12_IN15_34") (pintype "bidirectional"))
    )
    (net (code "80") (name "unconnected-(U4-PC13{slash}RTC_AF1-Pad7)") (class "Default")
      (node (ref "U4") (pin "7") (pinfunction "PC13/RTC_AF1_7") (pintype "bidirectional"))
    )
    (net (code "81") (name "unconnected-(U4-PC14{slash}OSC32_IN-Pad8)") (class "Default")
      (node (ref "U4") (pin "8") (pinfunction "PC14/OSC32_IN_8") (pintype "bidirectional"))
    )
    (net (code "82") (name "unconnected-(U4-PC15{slash}OSC32_OUT-Pad9)") (class "Default")
      (node (ref "U4") (pin "9") (pinfunction "PC15/OSC32_OUT_9") (pintype "bidirectional"))
    )
    (net (code "83") (name "unconnected-(U4-PD0{slash}FSMC_D2{slash}CAN1_RX-Pad81)") (class "Default")
      (node (ref "U4") (pin "81") (pinfunction "PD0/FSMC_D2/CAN1_RX_81") (pintype "bidirectional"))
    )
    (net (code "84") (name "unconnected-(U4-PD1FSMC_D3{slash}CAN1_TX-Pad82)") (class "Default")
      (node (ref "U4") (pin "82") (pinfunction "PD1FSMC_D3/CAN1_TX_82") (pintype "bidirectional"))
    )
    (net (code "85") (name "unconnected-(U4-PD3{slash}FSMC_CLK{slash}USART2_CTS-Pad84)") (class "Default")
      (node (ref "U4") (pin "84") (pinfunction "PD3/FSMC_CLK/USART2_CTS_84") (pintype "bidirectional"))
    )
    (net (code "86") (name "unconnected-(U4-PD7{slash}USART2_CK{slash}FSMC_NE1{slash}FSMC_NCE2-Pad88)") (class "Default")
      (node (ref "U4") (pin "88") (pinfunction "PD7/USART2_CK/FSMC_NE1/FSMC_NCE2_88") (pintype "bidirectional"))
    )
    (net (code "87") (name "unconnected-(U4-PD10{slash}FSMC_D15{slash}USART3_CK-Pad57)") (class "Default")
      (node (ref "U4") (pin "57") (pinfunction "PD10/FSMC_D15/USART3_CK_57") (pintype "bidirectional"))
    )
    (net (code "88") (name "unconnected-(U4-PD11{slash}FSMC_A16{slash}USART3_CTS-Pad58)") (class "Default")
      (node (ref "U4") (pin "58") (pinfunction "PD11/FSMC_A16/USART3_CTS_58") (pintype "bidirectional"))
    )
    (net (code "89") (name "unconnected-(U4-PD12{slash}FSMC_A17{slash}TIM4_CH1{slash}USART3_RTS-Pad59)") (class "Default")
      (node (ref "U4") (pin "59") (pinfunction "PD12/FSMC_A17/TIM4_CH1/USART3_RTS_59") (pintype "bidirectional"))
    )
    (net (code "90") (name "unconnected-(U4-PD13{slash}FSMC_A18{slash}TIM4_CH2-Pad60)") (class "Default")
      (node (ref "U4") (pin "60") (pinfunction "PD13/FSMC_A18/TIM4_CH2_60") (pintype "bidirectional"))
    )
    (net (code "91") (name "unconnected-(U4-PD14{slash}FSMC_D0{slash}TIM4_CH3-Pad61)") (class "Default")
      (node (ref "U4") (pin "61") (pinfunction "PD14/FSMC_D0/TIM4_CH3_61") (pintype "bidirectional"))
    )
    (net (code "92") (name "unconnected-(U4-PD15{slash}FSMC_D1{slash}TIM4_CH4-Pad62)") (class "Default")
      (node (ref "U4") (pin "62") (pinfunction "PD15/FSMC_D1/TIM4_CH4_62") (pintype "bidirectional"))
    )
    (net (code "93") (name "unconnected-(U4-PE2{slash}TRACECLK{slash}FSMC_A23{slash}ETH_MII_TXD3-Pad1)") (class "Default")
      (node (ref "U4") (pin "1") (pinfunction "PE2/TRACECLK/FSMC_A23/ETH_MII_TXD3_1") (pintype "bidirectional"))
    )
    (net (code "94") (name "unconnected-(U4-PE3{slash}TRACED0{slash}FSMC_A19-Pad2)") (class "Default")
      (node (ref "U4") (pin "2") (pinfunction "PE3/TRACED0/FSMC_A19_2") (pintype "bidirectional"))
    )
    (net (code "95") (name "unconnected-(U4-PE7{slash}FSMC_D4{slash}TIM1_ETR-Pad38)") (class "Default")
      (node (ref "U4") (pin "38") (pinfunction "PE7/FSMC_D4/TIM1_ETR_38") (pintype "bidirectional"))
    )
    (net (code "96") (name "unconnected-(U4-PE8{slash}FSMC_D5{slash}TIM1_CH1N-Pad39)") (class "Default")
      (node (ref "U4") (pin "39") (pinfunction "PE8/FSMC_D5/TIM1_CH1N_39") (pintype "bidirectional"))
    )
    (net (code "97") (name "unconnected-(U4-PE9{slash}FSMC_D6{slash}TIM1_CH1-Pad40)") (class "Default")
      (node (ref "U4") (pin "40") (pinfunction "PE9/FSMC_D6/TIM1_CH1_40") (pintype "bidirectional"))
    )
    (net (code "98") (name "unconnected-(U4-PE10{slash}FSMC_D7{slash}TIM1_CH2N-Pad41)") (class "Default")
      (node (ref "U4") (pin "41") (pinfunction "PE10/FSMC_D7/TIM1_CH2N_41") (pintype "bidirectional"))
    )
    (net (code "99") (name "unconnected-(U4-PE11{slash}FSMC_D8{slash}TIM1_CH2-Pad42)") (class "Default")
      (node (ref "U4") (pin "42") (pinfunction "PE11/FSMC_D8/TIM1_CH2_42") (pintype "bidirectional"))
    )
    (net (code "100") (name "unconnected-(U4-PE12{slash}FSMC_D9{slash}TIM1_CH3N-Pad43)") (class "Default")
      (node (ref "U4") (pin "43") (pinfunction "PE12/FSMC_D9/TIM1_CH3N_43") (pintype "bidirectional"))
    )
    (net (code "101") (name "unconnected-(U4-PE13{slash}FSMC_D10{slash}TIM1_CH3-Pad44)") (class "Default")
      (node (ref "U4") (pin "44") (pinfunction "PE13/FSMC_D10/TIM1_CH3_44") (pintype "bidirectional"))
    )
    (net (code "102") (name "unconnected-(U4-PE14{slash}FSMC_D11{slash}TIM1_CH4-Pad45)") (class "Default")
      (node (ref "U4") (pin "45") (pinfunction "PE14/FSMC_D11/TIM1_CH4_45") (pintype "bidirectional"))
    )
    (net (code "103") (name "unconnected-(U4-PE15FSMC_D12{slash}TIM1_BKIN-Pad46)") (class "Default")
      (node (ref "U4") (pin "46") (pinfunction "PE15FSMC_D12/TIM1_BKIN_46") (pintype "bidirectional"))
    )
  )
)
